# SCH_mev_battery_2023-11-28.net
KiCad netlist of a schematic drawn in EasyEDA
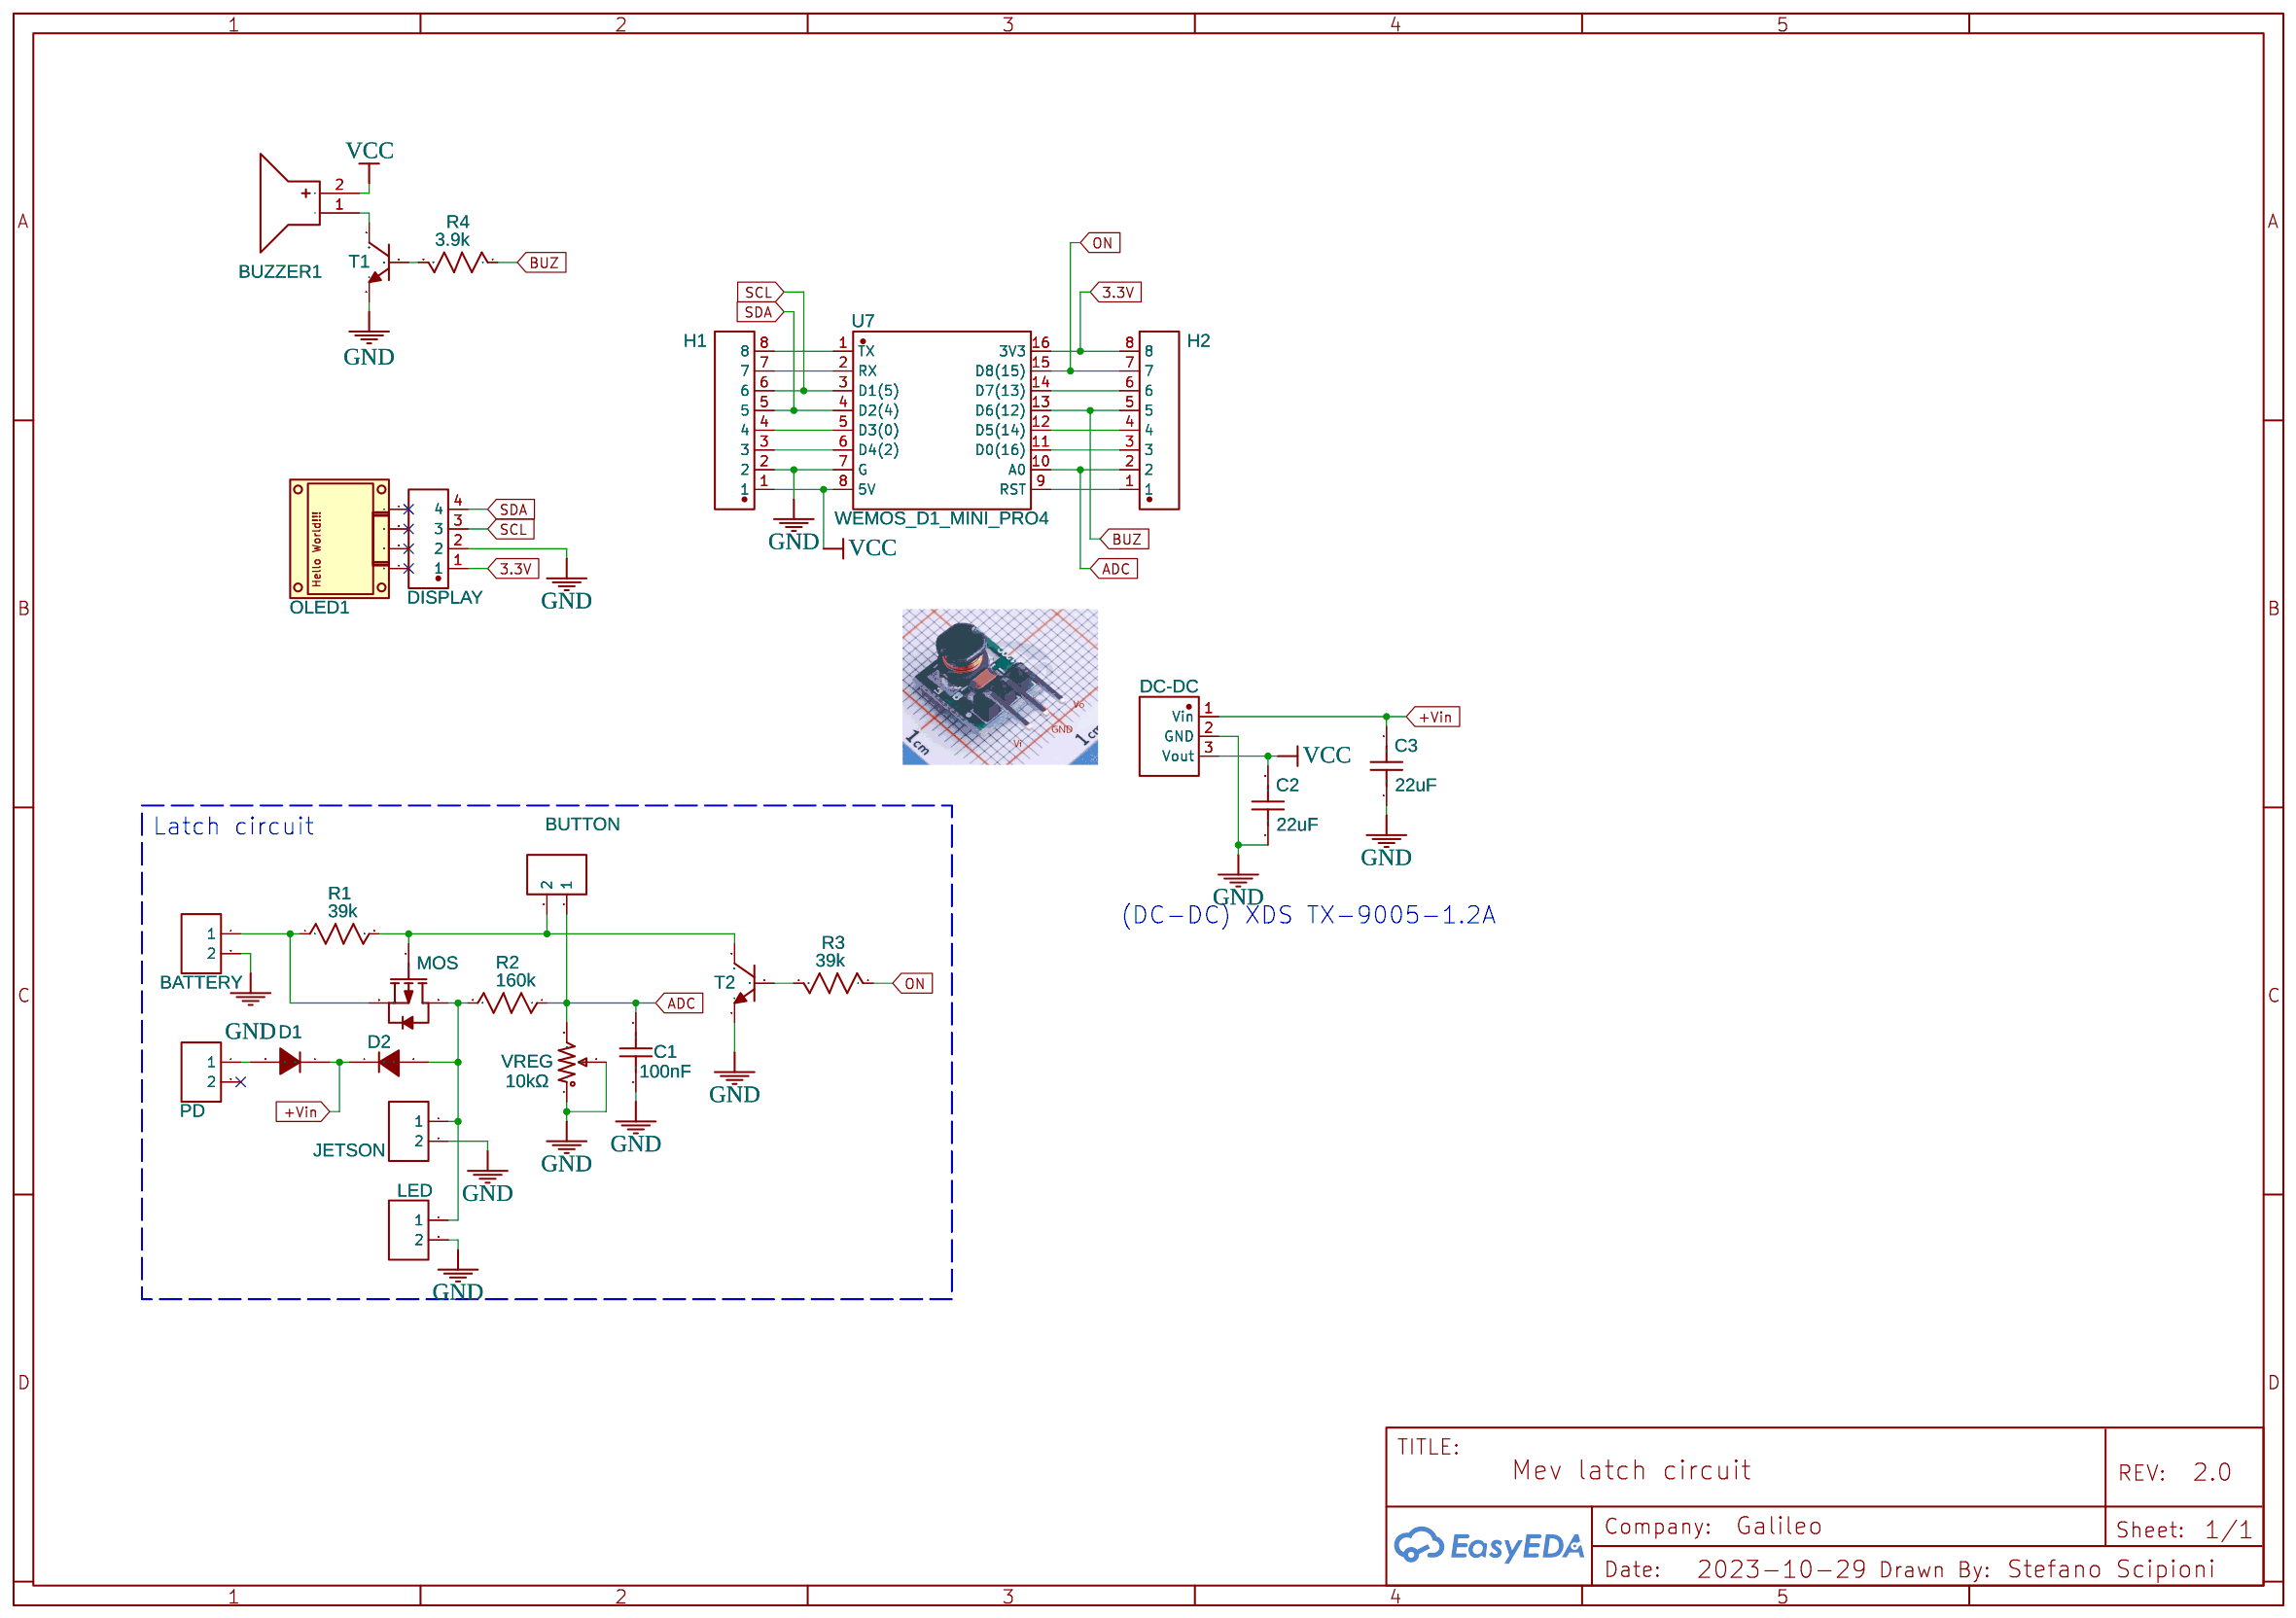
[diagram p0: schematic sheet]

(export (version "E")
  (design (tool "Eeschema 10.0.6"))
  (components
    (comp (ref "BATTERY") (value "+Battery") (libsource (lib "") (part "HDR-F-2.54_1x2_2")))
    (comp (ref "BUTTON") (value "Button") (libsource (lib "") (part "HDR-F-2.54_1x2_3")))
    (comp (ref "BUZZER1")
      (value "BUZZER")
      (fields (field (name "Manufacturer Part") "buzzer"))
      (libsource (lib "") (part "BUZZER"))
    )
    (comp (ref "C1")
      (value "100nF")
      (fields (field (name "Manufacturer Part") "C0805B104K500NT") (field (name "Manufacturer") "TORCH(火炬)"))
      (libsource (lib "") (part "C0805B104K500NT"))
    )
    (comp (ref "C2")
      (value "22uF")
      (fields
        (field (name "Manufacturer Part") "CL21A226MAYNNNE")
        (field (name "Manufacturer") "SAMSUNG(三星)")
      )
      (libsource (lib "") (part "CL21A226MAYNNNE"))
    )
    (comp (ref "C3")
      (value "22uF")
      (fields
        (field (name "Manufacturer Part") "CL21A226MAYNNNE")
        (field (name "Manufacturer") "SAMSUNG(三星)")
      )
      (libsource (lib "") (part "CL21A226MAYNNNE"))
    )
    (comp (ref "D1")
      (value "SD103AW_C5345965")
      (fields (field (name "Manufacturer Part") "SD103AW") (field (name "Manufacturer") "HXY MOSFET(华轩阳电子)"))
      (libsource (lib "") (part "SD103AW_C5345965_1"))
    )
    (comp (ref "D2")
      (value "SD103AW_C5345965")
      (fields (field (name "Manufacturer Part") "SD103AW") (field (name "Manufacturer") "HXY MOSFET(华轩阳电子)"))
      (libsource (lib "") (part "SD103AW_C5345965"))
    )
    (comp (ref "DC-DC")
      (value "DC-DC 5V")
      (fields
        (field (name "Manufacturer Part") "TLE4998S3XALA1")
        (field (name "Manufacturer") "Infineon(英飞凌)")
      )
      (libsource (lib "") (part "TLE4998S3XALA1"))
    )
    (comp (ref "DISPLAY")
      (value "DISPLAY")
      (fields (field (name "Manufacturer Part") "1X4P"))
      (libsource (lib "") (part "1X4P"))
    )
    (comp (ref "H1")
      (value "DS1023-1X8SF11")
      (fields (field (name "Manufacturer Part") "DS1023-1x8SF11") (field (name "Manufacturer") "CONNFLY"))
      (libsource (lib "") (part "DS1023-1X8SF11_1"))
    )
    (comp (ref "H2")
      (value "DS1023-1X8SF11")
      (fields (field (name "Manufacturer Part") "DS1023-1x8SF11") (field (name "Manufacturer") "CONNFLY"))
      (libsource (lib "") (part "DS1023-1X8SF11"))
    )
    (comp (ref "JETSON") (value "Jetson") (libsource (lib "") (part "HDR-F-2.54_1x2_4")))
    (comp (ref "LED") (value "LED") (libsource (lib "") (part "HDR-F-2.54_1x2")))
    (comp (ref "MOS")
      (value "AOD413A_C5261059")
      (fields (field (name "Manufacturer Part") "AOD413A") (field (name "Manufacturer") "HXY MOSFET(华轩阳电子)"))
      (libsource (lib "") (part "AOD413A_C5261059"))
    )
    (comp (ref "OLED1") (value "0.96OLED_4P") (libsource (lib "") (part "0.96OLED_4P")))
    (comp (ref "PD") (value "+PD") (libsource (lib "") (part "HDR-F-2.54_1x2_1")))
    (comp (ref "R1") (value "39k") (libsource (lib "") (part "R_0603_US_1")))
    (comp (ref "R2") (value "160k") (libsource (lib "") (part "R_0603_US_2")))
    (comp (ref "R3") (value "39k") (libsource (lib "") (part "R_0603_US")))
    (comp (ref "R4") (value "3.9k") (libsource (lib "") (part "R_0603_US")))
    (comp (ref "T1")
      (value "MMBT3904_C7603197")
      (fields (field (name "Manufacturer Part") "MMBT3904") (field (name "Manufacturer") "KUU(永裕泰)"))
      (libsource (lib "") (part "MMBT3904_C7603197"))
    )
    (comp (ref "T2")
      (value "MMBT3904_C7603197")
      (fields (field (name "Manufacturer Part") "MMBT3904") (field (name "Manufacturer") "KUU(永裕泰)"))
      (libsource (lib "") (part "MMBT3904_C7603197"))
    )
    (comp (ref "U7")
      (value "WEMOS_D1_MINI_PRO4")
      (fields (field (name "Manufacturer Part") "Wemos_D1_mini_Pro4"))
      (libsource (lib "") (part "WEMOS_D1_MINI_PRO4"))
    )
    (comp (ref "VREG")
      (value "10kΩ")
      (fields (field (name "Manufacturer Part") "TC33X-2-103E") (field (name "Manufacturer") "BOURNS"))
      (libsource (lib "") (part "TC33X-2-103E"))
    )
  )
  (nets
    (net (code "1") (name "+Vin") (class "Default")
      (node (ref "C3") (pin "2") (pinfunction "2_2") (pintype "unspecified"))
      (node (ref "D1") (pin "1") (pinfunction "C_1") (pintype "unspecified"))
      (node (ref "D2") (pin "1") (pinfunction "C_1") (pintype "unspecified"))
      (node (ref "DC-DC") (pin "1") (pinfunction "Vin_1") (pintype "unspecified"))
    )
    (net (code "2") (name "3.3V") (class "Default")
      (node (ref "DISPLAY") (pin "1") (pinfunction "1_1") (pintype "unspecified"))
      (node (ref "H2") (pin "8") (pinfunction "8_8") (pintype "unspecified"))
      (node (ref "U7") (pin "16") (pinfunction "3V3_16") (pintype "unspecified"))
    )
    (net (code "3") (name "ADC") (class "Default")
      (node (ref "BUTTON") (pin "1") (pinfunction "1_1") (pintype "input"))
      (node (ref "C1") (pin "1") (pinfunction "1_1") (pintype "unspecified"))
      (node (ref "H2") (pin "2") (pinfunction "2_2") (pintype "unspecified"))
      (node (ref "R2") (pin "1") (pinfunction "1_1") (pintype "unspecified"))
      (node (ref "U7") (pin "10") (pinfunction "A0_10") (pintype "unspecified"))
      (node (ref "VREG") (pin "3") (pinfunction "3_3") (pintype "unspecified"))
    )
    (net (code "4") (name "BUZ") (class "Default")
      (node (ref "H2") (pin "5") (pinfunction "5_5") (pintype "unspecified"))
      (node (ref "R4") (pin "1") (pinfunction "1_1") (pintype "unspecified"))
      (node (ref "U7") (pin "13") (pinfunction "D6(12)_13") (pintype "unspecified"))
    )
    (net (code "5") (name "GND") (class "Default")
      (node (ref "BATTERY") (pin "2") (pinfunction "2_2") (pintype "input"))
      (node (ref "C1") (pin "2") (pinfunction "2_2") (pintype "unspecified"))
      (node (ref "C2") (pin "1") (pinfunction "1_1") (pintype "unspecified"))
      (node (ref "C3") (pin "1") (pinfunction "1_1") (pintype "unspecified"))
      (node (ref "DC-DC") (pin "2") (pinfunction "GND_2") (pintype "unspecified"))
      (node (ref "DISPLAY") (pin "2") (pinfunction "2_2") (pintype "unspecified"))
      (node (ref "H1") (pin "2") (pinfunction "2_2") (pintype "unspecified"))
      (node (ref "JETSON") (pin "2") (pinfunction "2_2") (pintype "input"))
      (node (ref "LED") (pin "2") (pinfunction "2_2") (pintype "input"))
      (node (ref "T1") (pin "2") (pinfunction "E_2") (pintype "input"))
      (node (ref "T2") (pin "2") (pinfunction "E_2") (pintype "input"))
      (node (ref "U7") (pin "7") (pinfunction "G_7") (pintype "unspecified"))
      (node (ref "VREG") (pin "1") (pinfunction "1_1") (pintype "unspecified"))
      (node (ref "VREG") (pin "2") (pinfunction "2_2") (pintype "unspecified"))
    )
    (net (code "6") (name "Net-(BUZZER1--)") (class "Default")
      (node (ref "BUZZER1") (pin "1") (pinfunction "-_1") (pintype "unspecified"))
      (node (ref "T1") (pin "3") (pinfunction "C_3") (pintype "input"))
    )
    (net (code "7") (name "Net-(D1-A)") (class "Default")
      (node (ref "D1") (pin "2") (pinfunction "A_2") (pintype "unspecified"))
      (node (ref "PD") (pin "1") (pinfunction "1_1") (pintype "input"))
    )
    (net (code "8") (name "Net-(D2-A)") (class "Default")
      (node (ref "D2") (pin "2") (pinfunction "A_2") (pintype "unspecified"))
      (node (ref "JETSON") (pin "1") (pinfunction "1_1") (pintype "input"))
      (node (ref "LED") (pin "1") (pinfunction "1_1") (pintype "input"))
      (node (ref "MOS") (pin "2") (pinfunction "D_2") (pintype "unspecified"))
      (node (ref "R2") (pin "2") (pinfunction "2_2") (pintype "unspecified"))
    )
    (net (code "9") (name "Net-(MOS-G)") (class "Default")
      (node (ref "BUTTON") (pin "2") (pinfunction "2_2") (pintype "input"))
      (node (ref "MOS") (pin "1") (pinfunction "G_1") (pintype "unspecified"))
      (node (ref "R1") (pin "2") (pinfunction "2_2") (pintype "unspecified"))
      (node (ref "T2") (pin "3") (pinfunction "C_3") (pintype "input"))
    )
    (net (code "10") (name "Net-(MOS-S)") (class "Default")
      (node (ref "BATTERY") (pin "1") (pinfunction "1_1") (pintype "input"))
      (node (ref "MOS") (pin "3") (pinfunction "S_3") (pintype "unspecified"))
      (node (ref "R1") (pin "1") (pinfunction "1_1") (pintype "unspecified"))
    )
    (net (code "11") (name "Net-(T1-B)") (class "Default")
      (node (ref "R4") (pin "2") (pinfunction "2_2") (pintype "unspecified"))
      (node (ref "T1") (pin "1") (pinfunction "B_1") (pintype "input"))
    )
    (net (code "12") (name "Net-(T2-B)") (class "Default")
      (node (ref "R3") (pin "2") (pinfunction "2_2") (pintype "unspecified"))
      (node (ref "T2") (pin "1") (pinfunction "B_1") (pintype "input"))
    )
    (net (code "13") (name "Net-(U7-D0(16))") (class "Default")
      (node (ref "H2") (pin "3") (pinfunction "3_3") (pintype "unspecified"))
      (node (ref "U7") (pin "11") (pinfunction "D0(16)_11") (pintype "unspecified"))
    )
    (net (code "14") (name "Net-(U7-D3(0))") (class "Default")
      (node (ref "H1") (pin "4") (pinfunction "4_4") (pintype "unspecified"))
      (node (ref "U7") (pin "5") (pinfunction "D3(0)_5") (pintype "unspecified"))
    )
    (net (code "15") (name "Net-(U7-D4(2))") (class "Default")
      (node (ref "H1") (pin "3") (pinfunction "3_3") (pintype "unspecified"))
      (node (ref "U7") (pin "6") (pinfunction "D4(2)_6") (pintype "unspecified"))
    )
    (net (code "16") (name "Net-(U7-D5(14))") (class "Default")
      (node (ref "H2") (pin "4") (pinfunction "4_4") (pintype "unspecified"))
      (node (ref "U7") (pin "12") (pinfunction "D5(14)_12") (pintype "unspecified"))
    )
    (net (code "17") (name "Net-(U7-D7(13))") (class "Default")
      (node (ref "H2") (pin "6") (pinfunction "6_6") (pintype "unspecified"))
      (node (ref "U7") (pin "14") (pinfunction "D7(13)_14") (pintype "unspecified"))
    )
    (net (code "18") (name "Net-(U7-RST)") (class "Default")
      (node (ref "H2") (pin "1") (pinfunction "1_1") (pintype "unspecified"))
      (node (ref "U7") (pin "9") (pinfunction "RST_9") (pintype "unspecified"))
    )
    (net (code "19") (name "Net-(U7-RX)") (class "Default")
      (node (ref "H1") (pin "7") (pinfunction "7_7") (pintype "unspecified"))
      (node (ref "U7") (pin "2") (pinfunction "RX_2") (pintype "unspecified"))
    )
    (net (code "20") (name "Net-(U7-TX)") (class "Default")
      (node (ref "H1") (pin "8") (pinfunction "8_8") (pintype "unspecified"))
      (node (ref "U7") (pin "1") (pinfunction "TX_1") (pintype "unspecified"))
    )
    (net (code "21") (name "ON") (class "Default")
      (node (ref "H2") (pin "7") (pinfunction "7_7") (pintype "unspecified"))
      (node (ref "R3") (pin "1") (pinfunction "1_1") (pintype "unspecified"))
      (node (ref "U7") (pin "15") (pinfunction "D8(15)_15") (pintype "unspecified"))
    )
    (net (code "22") (name "SCL") (class "Default")
      (node (ref "DISPLAY") (pin "3") (pinfunction "3_3") (pintype "unspecified"))
      (node (ref "H1") (pin "6") (pinfunction "6_6") (pintype "unspecified"))
      (node (ref "U7") (pin "3") (pinfunction "D1(5)_3") (pintype "unspecified"))
    )
    (net (code "23") (name "SDA") (class "Default")
      (node (ref "DISPLAY") (pin "4") (pinfunction "4_4") (pintype "unspecified"))
      (node (ref "H1") (pin "5") (pinfunction "5_5") (pintype "unspecified"))
      (node (ref "U7") (pin "4") (pinfunction "D2(4)_4") (pintype "unspecified"))
    )
    (net (code "24") (name "VCC") (class "Default")
      (node (ref "BUZZER1") (pin "2") (pinfunction "+_2") (pintype "unspecified"))
      (node (ref "C2") (pin "2") (pinfunction "2_2") (pintype "unspecified"))
      (node (ref "DC-DC") (pin "3") (pinfunction "Vout_3") (pintype "unspecified"))
      (node (ref "H1") (pin "1") (pinfunction "1_1") (pintype "unspecified"))
      (node (ref "U7") (pin "8") (pinfunction "5V_8") (pintype "unspecified"))
    )
    (net (code "25") (name "unconnected-(OLED1-Pad1)") (class "Default")
      (node (ref "OLED1") (pin "1") (pinfunction "1_1") (pintype "unspecified+no_connect"))
    )
    (net (code "26") (name "unconnected-(OLED1-Pad2)") (class "Default")
      (node (ref "OLED1") (pin "2") (pinfunction "2_2") (pintype "unspecified+no_connect"))
    )
    (net (code "27") (name "unconnected-(OLED1-Pad3)") (class "Default")
      (node (ref "OLED1") (pin "3") (pinfunction "3_3") (pintype "unspecified+no_connect"))
    )
    (net (code "28") (name "unconnected-(OLED1-Pad4)") (class "Default")
      (node (ref "OLED1") (pin "4") (pinfunction "4_4") (pintype "unspecified+no_connect"))
    )
    (net (code "29") (name "unconnected-(PD-Pad2)") (class "Default")
      (node (ref "PD") (pin "2") (pinfunction "2_2") (pintype "input+no_connect"))
    )
  )
)
